# IMD_BMS.net
KiCad netlist of a schematic drawn in EAGLE
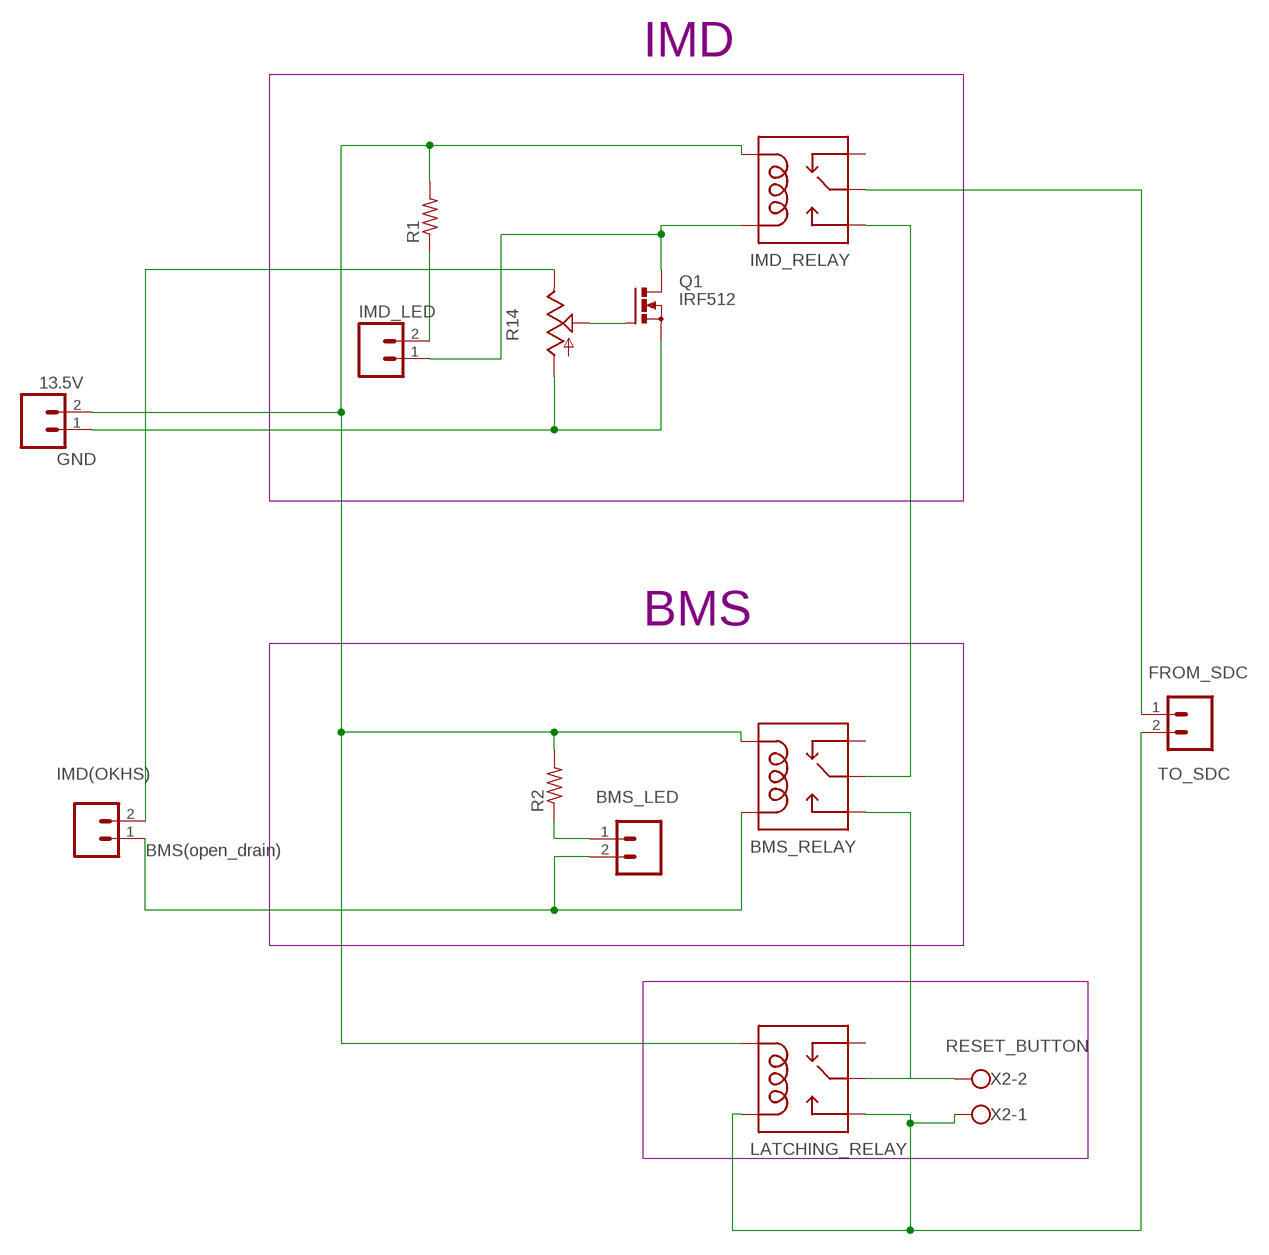
[diagram p0: schematic, sheet 1]

(export (version "E")
  (design (tool "Eeschema 10.0.6"))
  (components
    (comp (ref "13.5V")
      (value "GND")
      (footprint "eagle-import:02P")
      (libsource (lib "eagle-import") (part "M02"))
    )
    (comp (ref "BMS_LED")
      (value "M02")
      (footprint "eagle-import:02P")
      (libsource (lib "eagle-import") (part "M02"))
    )
    (comp (ref "FROM_SDC")
      (value "TO_SDC")
      (footprint "eagle-import:02P")
      (libsource (lib "eagle-import") (part "M02"))
    )
    (comp (ref "IMD(OKHS)")
      (value "BMS(open_drain)")
      (footprint "eagle-import:02P")
      (libsource (lib "eagle-import") (part "M02"))
    )
    (comp (ref "IMD_LED")
      (value "M02")
      (footprint "eagle-import:02P")
      (libsource (lib "eagle-import") (part "M02"))
    )
    (comp (ref "K1")
      (value "BMS_RELAY")
      (footprint "eagle-import:RELAY_G5LE")
      (libsource (lib "eagle-import") (part "RELAY-SPDT"))
    )
    (comp (ref "K2")
      (value "LATCHING_RELAY")
      (footprint "eagle-import:RELAY_G5LE")
      (libsource (lib "eagle-import") (part "RELAY-SPDT"))
    )
    (comp (ref "K3")
      (value "IMD_RELAY")
      (footprint "eagle-import:RELAY_G5LE")
      (libsource (lib "eagle-import") (part "RELAY-SPDT"))
    )
    (comp (ref "Q1")
      (value "IRF512")
      (footprint "eagle-import:TO220BV")
      (libsource (lib "eagle-import") (part "IRF512"))
    )
    (comp (ref "R1")
      (value "R-US_0204/5")
      (footprint "eagle-import:0204_5")
      (libsource (lib "eagle-import") (part "R-US_0204/5"))
    )
    (comp (ref "R2")
      (value "R-US_0204/5")
      (footprint "eagle-import:0204_5")
      (libsource (lib "eagle-import") (part "R-US_0204/5"))
    )
    (comp (ref "R14")
      (value "TRIM_US-B25P")
      (footprint "eagle-import:B25P")
      (libsource (lib "eagle-import") (part "TRIM_US-B25P"))
    )
    (comp (ref "X2")
      (value "W237-102")
      (footprint "eagle-import:W237-102")
      (fields (field (name "MPN") "237-102"))
      (libsource (lib "eagle-import") (part "W237-102"))
    )
  )
  (nets
    (net (code "1") (name "/RESET_BUTTON") (class "Default")
      (node (ref "K1") (pin "3") (pinfunction "NO_3") (pintype "bidirectional"))
      (node (ref "K2") (pin "1") (pinfunction "MAIN_1") (pintype "bidirectional"))
      (node (ref "X2") (pin "2") (pinfunction "KL_2") (pintype "passive"))
    )
    (net (code "2") (name "Net-(13.5V-Pad1)") (class "Default")
      (node (ref "13.5V") (pin "1") (pinfunction "1_1") (pintype "passive"))
      (node (ref "Q1") (pin "S") (pinfunction "S_S") (pintype "passive"))
      (node (ref "R14") (pin "A") (pinfunction "A_A") (pintype "passive"))
    )
    (net (code "3") (name "Net-(BMS_LED-Pad1)") (class "Default")
      (node (ref "BMS_LED") (pin "1") (pinfunction "1_1") (pintype "passive"))
      (node (ref "R2") (pin "1") (pinfunction "1_1") (pintype "passive"))
    )
    (net (code "4") (name "Net-(IMD(OKHS)-Pad2)") (class "Default")
      (node (ref "IMD(OKHS)") (pin "2") (pinfunction "2_2") (pintype "passive"))
      (node (ref "R14") (pin "E") (pinfunction "E_E") (pintype "passive"))
    )
    (net (code "5") (name "Net-(IMD_LED-Pad2)") (class "Default")
      (node (ref "IMD_LED") (pin "2") (pinfunction "2_2") (pintype "passive"))
      (node (ref "R1") (pin "1") (pinfunction "1_1") (pintype "passive"))
    )
    (net (code "6") (name "Net-(K1-COIL1)") (class "Default")
      (node (ref "13.5V") (pin "2") (pinfunction "2_2") (pintype "passive"))
      (node (ref "K1") (pin "2") (pinfunction "COIL1_2") (pintype "bidirectional"))
      (node (ref "K2") (pin "2") (pinfunction "COIL1_2") (pintype "bidirectional"))
      (node (ref "K3") (pin "2") (pinfunction "COIL1_2") (pintype "bidirectional"))
      (node (ref "R1") (pin "2") (pinfunction "2_2") (pintype "passive"))
      (node (ref "R2") (pin "2") (pinfunction "2_2") (pintype "passive"))
    )
    (net (code "7") (name "Net-(K1-COIL2)") (class "Default")
      (node (ref "BMS_LED") (pin "2") (pinfunction "2_2") (pintype "passive"))
      (node (ref "IMD(OKHS)") (pin "1") (pinfunction "1_1") (pintype "passive"))
      (node (ref "K1") (pin "5") (pinfunction "COIL2_5") (pintype "bidirectional"))
    )
    (net (code "8") (name "Net-(K1-MAIN)") (class "Default")
      (node (ref "K1") (pin "1") (pinfunction "MAIN_1") (pintype "bidirectional"))
      (node (ref "K3") (pin "3") (pinfunction "NO_3") (pintype "bidirectional"))
    )
    (net (code "9") (name "Net-(K2-COIL2)") (class "Default")
      (node (ref "FROM_SDC") (pin "2") (pinfunction "2_2") (pintype "passive"))
      (node (ref "K2") (pin "3") (pinfunction "NO_3") (pintype "bidirectional"))
      (node (ref "K2") (pin "5") (pinfunction "COIL2_5") (pintype "bidirectional"))
      (node (ref "X2") (pin "1") (pinfunction "KL_1") (pintype "passive"))
    )
    (net (code "10") (name "Net-(K3-COIL2)") (class "Default")
      (node (ref "IMD_LED") (pin "1") (pinfunction "1_1") (pintype "passive"))
      (node (ref "K3") (pin "5") (pinfunction "COIL2_5") (pintype "bidirectional"))
      (node (ref "Q1") (pin "D") (pinfunction "D_D") (pintype "passive"))
    )
    (net (code "11") (name "Net-(K3-MAIN)") (class "Default")
      (node (ref "FROM_SDC") (pin "1") (pinfunction "1_1") (pintype "passive"))
      (node (ref "K3") (pin "1") (pinfunction "MAIN_1") (pintype "bidirectional"))
    )
    (net (code "12") (name "Net-(Q1-PadG)") (class "Default")
      (node (ref "Q1") (pin "G") (pinfunction "G_G") (pintype "passive"))
      (node (ref "R14") (pin "S") (pinfunction "S_S") (pintype "passive"))
    )
    (net (code "13") (name "unconnected-(K1-NC-Pad4)") (class "Default")
      (node (ref "K1") (pin "4") (pinfunction "NC_4") (pintype "bidirectional"))
    )
    (net (code "14") (name "unconnected-(K2-NC-Pad4)") (class "Default")
      (node (ref "K2") (pin "4") (pinfunction "NC_4") (pintype "bidirectional"))
    )
    (net (code "15") (name "unconnected-(K3-NC-Pad4)") (class "Default")
      (node (ref "K3") (pin "4") (pinfunction "NC_4") (pintype "bidirectional"))
    )
  )
)
